# freesoc2_shield.net
KiCad netlist of a schematic drawn in EAGLE
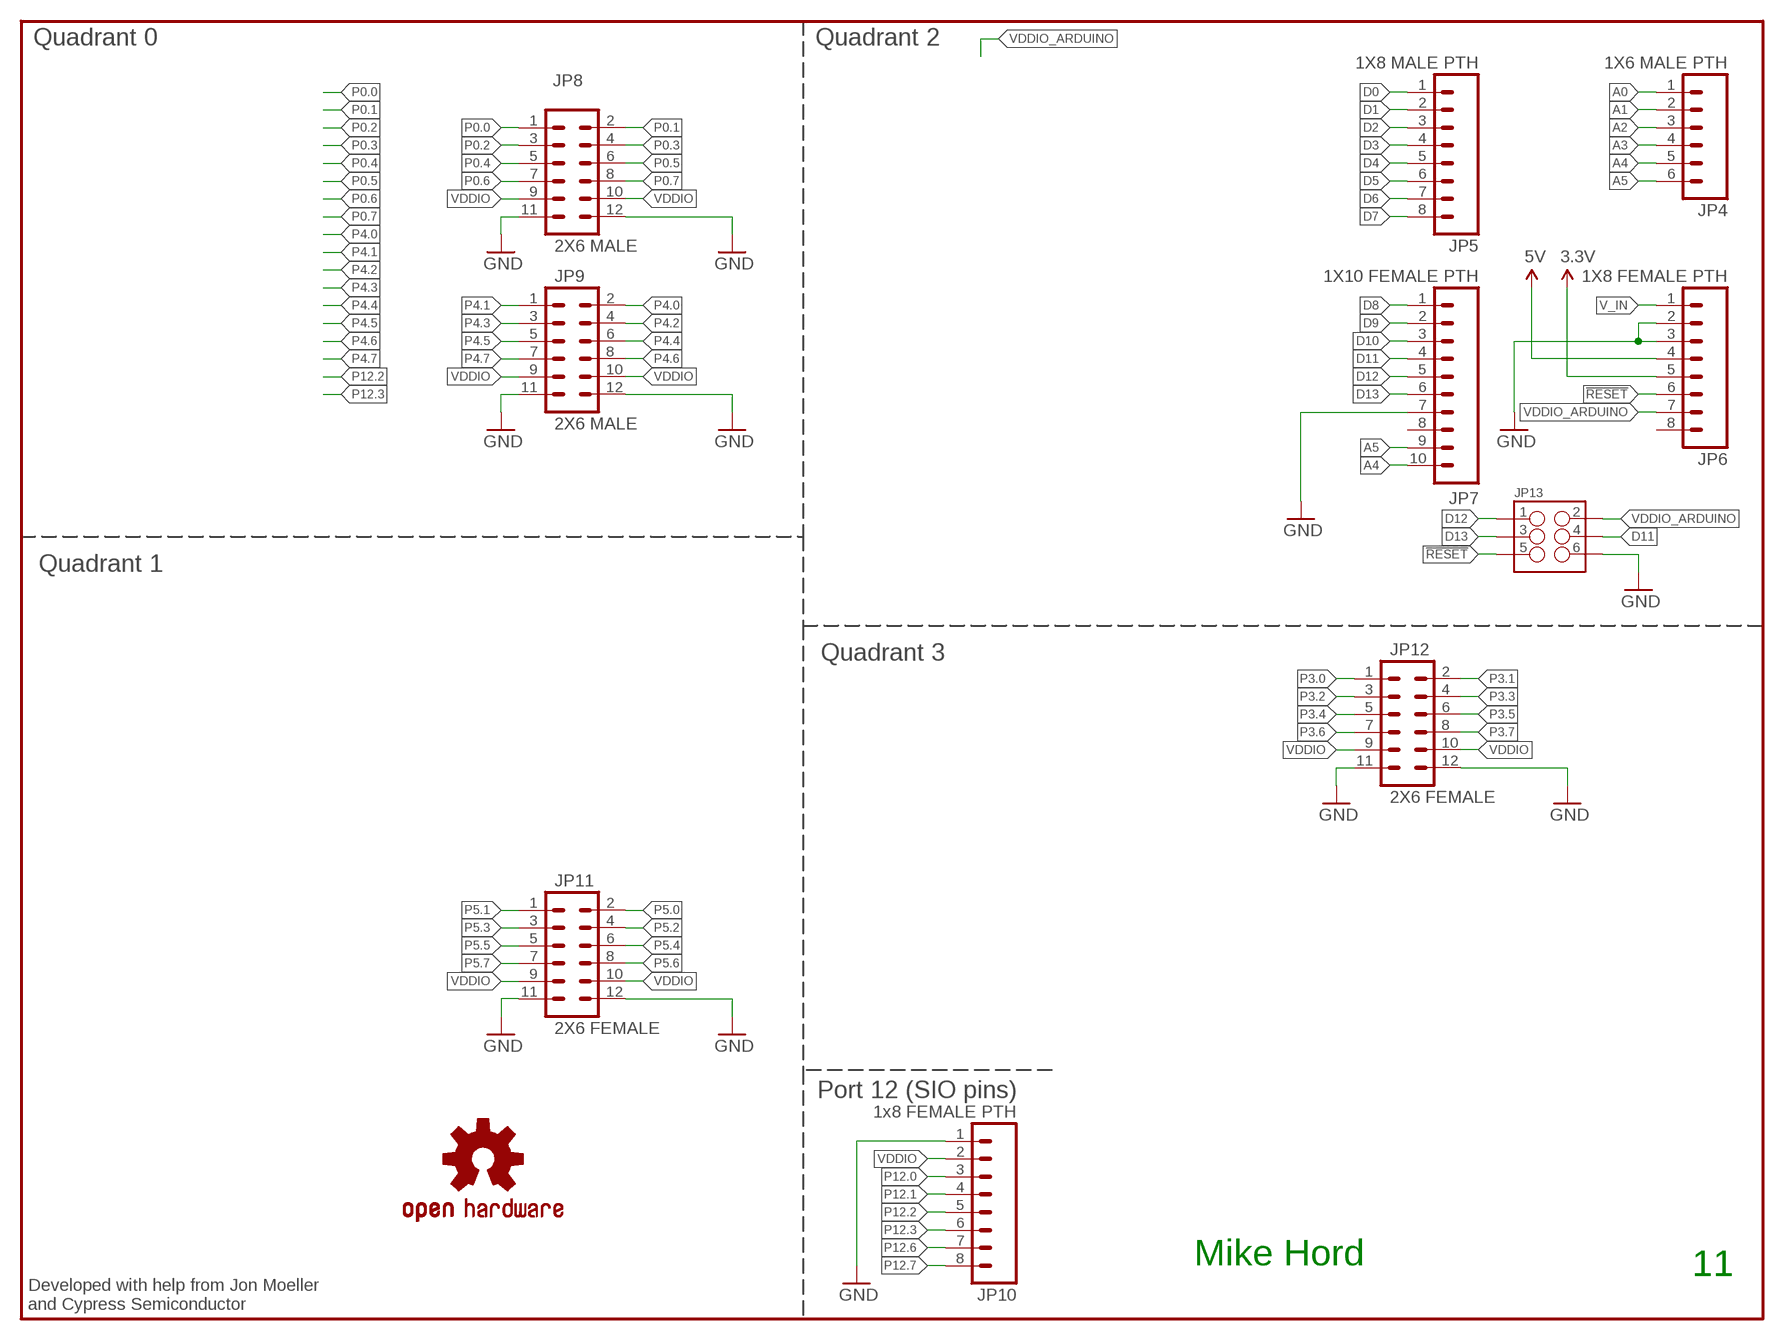
[diagram p0: schematic, sheet 1]

(export (version "E")
  (design (tool "Eeschema 10.0.6"))
  (components
    (comp (ref "FRAME1")
      (value "FRAME-LETTERNO_PACKAGE")
      (footprint "eagle-import:DUMMY")
      (fields (field (name "DESIGNER") "Nobody"))
      (libsource (lib "eagle-import") (part "FRAME-LETTERNO_PACKAGE"))
    )
    (comp (ref "JP4")
      (value "1X6 MALE PTH")
      (footprint "eagle-import:1X06-SIP_LOCK")
      (libsource (lib "eagle-import") (part "M06SIP_LOCK"))
    )
    (comp (ref "JP5")
      (value "1X8 MALE PTH")
      (footprint "eagle-import:1X08_LOCK")
      (libsource (lib "eagle-import") (part "M08LOCK"))
    )
    (comp (ref "JP6")
      (value "1X8 FEMALE PTH")
      (footprint "eagle-import:1X08_LOCK")
      (libsource (lib "eagle-import") (part "M08LOCK"))
    )
    (comp (ref "JP7")
      (value "1X10 FEMALE PTH")
      (footprint "eagle-import:1X10_LOCK")
      (libsource (lib "eagle-import") (part "M10LOCK"))
    )
    (comp (ref "JP8")
      (value "2X6 MALE")
      (footprint "eagle-import:2X6")
      (libsource (lib "eagle-import") (part "M06X2PTH_FEMALE"))
    )
    (comp (ref "JP9")
      (value "2X6 MALE")
      (footprint "eagle-import:2X6")
      (libsource (lib "eagle-import") (part "M06X2PTH_FEMALE"))
    )
    (comp (ref "JP10")
      (value "1x8 FEMALE PTH")
      (footprint "eagle-import:1X08_LOCK")
      (libsource (lib "eagle-import") (part "M08LOCK"))
    )
    (comp (ref "JP11")
      (value "2X6 FEMALE")
      (footprint "eagle-import:2X6")
      (libsource (lib "eagle-import") (part "M06X2PTH_FEMALE"))
    )
    (comp (ref "JP12")
      (value "2X6 FEMALE")
      (footprint "eagle-import:2X6")
      (libsource (lib "eagle-import") (part "M06X2PTH_FEMALE"))
    )
    (comp (ref "JP13")
      (value "M03X22X3_SILK_MALE_PTH")
      (footprint "eagle-import:2X3")
      (libsource (lib "eagle-import") (part "M03X22X3_SILK_MALE_PTH"))
    )
    (comp (ref "LOGO2")
      (value "OSHW-LOGOS")
      (footprint "eagle-import:OSHW-LOGO-S")
      (libsource (lib "eagle-import") (part "OSHW-LOGOS"))
    )
  )
  (nets
    (net (code "1") (name "/~{RESET}") (class "Default")
      (node (ref "JP13") (pin "5") (pinfunction "5_5") (pintype "bidirectional"))
      (node (ref "JP6") (pin "6") (pinfunction "6_6") (pintype "passive"))
    )
    (net (code "2") (name "3.3V") (class "Default")
      (node (ref "JP6") (pin "5") (pinfunction "5_5") (pintype "passive"))
    )
    (net (code "3") (name "5V") (class "Default")
      (node (ref "JP6") (pin "4") (pinfunction "4_4") (pintype "passive"))
    )
    (net (code "4") (name "A0") (class "Default")
      (node (ref "JP4") (pin "1") (pinfunction "1_1") (pintype "passive"))
    )
    (net (code "5") (name "A1") (class "Default")
      (node (ref "JP4") (pin "2") (pinfunction "2_2") (pintype "passive"))
    )
    (net (code "6") (name "A2") (class "Default")
      (node (ref "JP4") (pin "3") (pinfunction "3_3") (pintype "passive"))
    )
    (net (code "7") (name "A3") (class "Default")
      (node (ref "JP4") (pin "4") (pinfunction "4_4") (pintype "passive"))
    )
    (net (code "8") (name "A4") (class "Default")
      (node (ref "JP4") (pin "5") (pinfunction "5_5") (pintype "passive"))
      (node (ref "JP7") (pin "10") (pinfunction "10_10") (pintype "passive"))
    )
    (net (code "9") (name "A5") (class "Default")
      (node (ref "JP4") (pin "6") (pinfunction "6_6") (pintype "passive"))
      (node (ref "JP7") (pin "9") (pinfunction "9_9") (pintype "passive"))
    )
    (net (code "10") (name "D0") (class "Default")
      (node (ref "JP5") (pin "1") (pinfunction "1_1") (pintype "passive"))
    )
    (net (code "11") (name "D1") (class "Default")
      (node (ref "JP5") (pin "2") (pinfunction "2_2") (pintype "passive"))
    )
    (net (code "12") (name "D2") (class "Default")
      (node (ref "JP5") (pin "3") (pinfunction "3_3") (pintype "passive"))
    )
    (net (code "13") (name "D3") (class "Default")
      (node (ref "JP5") (pin "4") (pinfunction "4_4") (pintype "passive"))
    )
    (net (code "14") (name "D4") (class "Default")
      (node (ref "JP5") (pin "5") (pinfunction "5_5") (pintype "passive"))
    )
    (net (code "15") (name "D5") (class "Default")
      (node (ref "JP5") (pin "6") (pinfunction "6_6") (pintype "passive"))
    )
    (net (code "16") (name "D6") (class "Default")
      (node (ref "JP5") (pin "7") (pinfunction "7_7") (pintype "passive"))
    )
    (net (code "17") (name "D7") (class "Default")
      (node (ref "JP5") (pin "8") (pinfunction "8_8") (pintype "passive"))
    )
    (net (code "18") (name "D8") (class "Default")
      (node (ref "JP7") (pin "1") (pinfunction "1_1") (pintype "passive"))
    )
    (net (code "19") (name "D9") (class "Default")
      (node (ref "JP7") (pin "2") (pinfunction "2_2") (pintype "passive"))
    )
    (net (code "20") (name "D10") (class "Default")
      (node (ref "JP7") (pin "3") (pinfunction "3_3") (pintype "passive"))
    )
    (net (code "21") (name "D11") (class "Default")
      (node (ref "JP13") (pin "4") (pinfunction "4_4") (pintype "bidirectional"))
      (node (ref "JP7") (pin "4") (pinfunction "4_4") (pintype "passive"))
    )
    (net (code "22") (name "D12") (class "Default")
      (node (ref "JP13") (pin "1") (pinfunction "1_1") (pintype "bidirectional"))
      (node (ref "JP7") (pin "5") (pinfunction "5_5") (pintype "passive"))
    )
    (net (code "23") (name "D13") (class "Default")
      (node (ref "JP13") (pin "3") (pinfunction "3_3") (pintype "bidirectional"))
      (node (ref "JP7") (pin "6") (pinfunction "6_6") (pintype "passive"))
    )
    (net (code "24") (name "GND") (class "Default")
      (node (ref "JP10") (pin "1") (pinfunction "1_1") (pintype "passive"))
      (node (ref "JP11") (pin "11") (pinfunction "11_11") (pintype "passive"))
      (node (ref "JP11") (pin "12") (pinfunction "12_12") (pintype "passive"))
      (node (ref "JP12") (pin "11") (pinfunction "11_11") (pintype "passive"))
      (node (ref "JP12") (pin "12") (pinfunction "12_12") (pintype "passive"))
      (node (ref "JP13") (pin "6") (pinfunction "6_6") (pintype "bidirectional"))
      (node (ref "JP6") (pin "2") (pinfunction "2_2") (pintype "passive"))
      (node (ref "JP6") (pin "3") (pinfunction "3_3") (pintype "passive"))
      (node (ref "JP7") (pin "7") (pinfunction "7_7") (pintype "passive"))
      (node (ref "JP8") (pin "11") (pinfunction "11_11") (pintype "passive"))
      (node (ref "JP8") (pin "12") (pinfunction "12_12") (pintype "passive"))
      (node (ref "JP9") (pin "11") (pinfunction "11_11") (pintype "passive"))
      (node (ref "JP9") (pin "12") (pinfunction "12_12") (pintype "passive"))
    )
    (net (code "25") (name "P0.0") (class "Default")
      (node (ref "JP8") (pin "1") (pinfunction "1_1") (pintype "passive"))
    )
    (net (code "26") (name "P0.1") (class "Default")
      (node (ref "JP8") (pin "2") (pinfunction "2_2") (pintype "passive"))
    )
    (net (code "27") (name "P0.2") (class "Default")
      (node (ref "JP8") (pin "3") (pinfunction "3_3") (pintype "passive"))
    )
    (net (code "28") (name "P0.3") (class "Default")
      (node (ref "JP8") (pin "4") (pinfunction "4_4") (pintype "passive"))
    )
    (net (code "29") (name "P0.4") (class "Default")
      (node (ref "JP8") (pin "5") (pinfunction "5_5") (pintype "passive"))
    )
    (net (code "30") (name "P0.5") (class "Default")
      (node (ref "JP8") (pin "6") (pinfunction "6_6") (pintype "passive"))
    )
    (net (code "31") (name "P0.6") (class "Default")
      (node (ref "JP8") (pin "7") (pinfunction "7_7") (pintype "passive"))
    )
    (net (code "32") (name "P0.7") (class "Default")
      (node (ref "JP8") (pin "8") (pinfunction "8_8") (pintype "passive"))
    )
    (net (code "33") (name "P3.0") (class "Default")
      (node (ref "JP12") (pin "1") (pinfunction "1_1") (pintype "passive"))
    )
    (net (code "34") (name "P3.1") (class "Default")
      (node (ref "JP12") (pin "2") (pinfunction "2_2") (pintype "passive"))
    )
    (net (code "35") (name "P3.2") (class "Default")
      (node (ref "JP12") (pin "3") (pinfunction "3_3") (pintype "passive"))
    )
    (net (code "36") (name "P3.3") (class "Default")
      (node (ref "JP12") (pin "4") (pinfunction "4_4") (pintype "passive"))
    )
    (net (code "37") (name "P3.4") (class "Default")
      (node (ref "JP12") (pin "5") (pinfunction "5_5") (pintype "passive"))
    )
    (net (code "38") (name "P3.5") (class "Default")
      (node (ref "JP12") (pin "6") (pinfunction "6_6") (pintype "passive"))
    )
    (net (code "39") (name "P3.6") (class "Default")
      (node (ref "JP12") (pin "7") (pinfunction "7_7") (pintype "passive"))
    )
    (net (code "40") (name "P3.7") (class "Default")
      (node (ref "JP12") (pin "8") (pinfunction "8_8") (pintype "passive"))
    )
    (net (code "41") (name "P4.0") (class "Default")
      (node (ref "JP9") (pin "2") (pinfunction "2_2") (pintype "passive"))
    )
    (net (code "42") (name "P4.1") (class "Default")
      (node (ref "JP9") (pin "1") (pinfunction "1_1") (pintype "passive"))
    )
    (net (code "43") (name "P4.2") (class "Default")
      (node (ref "JP9") (pin "4") (pinfunction "4_4") (pintype "passive"))
    )
    (net (code "44") (name "P4.3") (class "Default")
      (node (ref "JP9") (pin "3") (pinfunction "3_3") (pintype "passive"))
    )
    (net (code "45") (name "P4.4") (class "Default")
      (node (ref "JP9") (pin "6") (pinfunction "6_6") (pintype "passive"))
    )
    (net (code "46") (name "P4.5") (class "Default")
      (node (ref "JP9") (pin "5") (pinfunction "5_5") (pintype "passive"))
    )
    (net (code "47") (name "P4.6") (class "Default")
      (node (ref "JP9") (pin "8") (pinfunction "8_8") (pintype "passive"))
    )
    (net (code "48") (name "P4.7") (class "Default")
      (node (ref "JP9") (pin "7") (pinfunction "7_7") (pintype "passive"))
    )
    (net (code "49") (name "P5.0") (class "Default")
      (node (ref "JP11") (pin "2") (pinfunction "2_2") (pintype "passive"))
    )
    (net (code "50") (name "P5.1") (class "Default")
      (node (ref "JP11") (pin "1") (pinfunction "1_1") (pintype "passive"))
    )
    (net (code "51") (name "P5.2") (class "Default")
      (node (ref "JP11") (pin "4") (pinfunction "4_4") (pintype "passive"))
    )
    (net (code "52") (name "P5.3") (class "Default")
      (node (ref "JP11") (pin "3") (pinfunction "3_3") (pintype "passive"))
    )
    (net (code "53") (name "P5.4") (class "Default")
      (node (ref "JP11") (pin "6") (pinfunction "6_6") (pintype "passive"))
    )
    (net (code "54") (name "P5.5") (class "Default")
      (node (ref "JP11") (pin "5") (pinfunction "5_5") (pintype "passive"))
    )
    (net (code "55") (name "P5.6") (class "Default")
      (node (ref "JP11") (pin "8") (pinfunction "8_8") (pintype "passive"))
    )
    (net (code "56") (name "P5.7") (class "Default")
      (node (ref "JP11") (pin "7") (pinfunction "7_7") (pintype "passive"))
    )
    (net (code "57") (name "P12.0") (class "Default")
      (node (ref "JP10") (pin "3") (pinfunction "3_3") (pintype "passive"))
    )
    (net (code "58") (name "P12.1") (class "Default")
      (node (ref "JP10") (pin "4") (pinfunction "4_4") (pintype "passive"))
    )
    (net (code "59") (name "P12.2") (class "Default")
      (node (ref "JP10") (pin "5") (pinfunction "5_5") (pintype "passive"))
    )
    (net (code "60") (name "P12.3") (class "Default")
      (node (ref "JP10") (pin "6") (pinfunction "6_6") (pintype "passive"))
    )
    (net (code "61") (name "P12.6") (class "Default")
      (node (ref "JP10") (pin "7") (pinfunction "7_7") (pintype "passive"))
    )
    (net (code "62") (name "P12.7") (class "Default")
      (node (ref "JP10") (pin "8") (pinfunction "8_8") (pintype "passive"))
    )
    (net (code "63") (name "VDDIO") (class "Default")
      (node (ref "JP10") (pin "2") (pinfunction "2_2") (pintype "passive"))
      (node (ref "JP11") (pin "10") (pinfunction "10_10") (pintype "passive"))
      (node (ref "JP11") (pin "9") (pinfunction "9_9") (pintype "passive"))
      (node (ref "JP12") (pin "10") (pinfunction "10_10") (pintype "passive"))
      (node (ref "JP12") (pin "9") (pinfunction "9_9") (pintype "passive"))
      (node (ref "JP8") (pin "10") (pinfunction "10_10") (pintype "passive"))
      (node (ref "JP8") (pin "9") (pinfunction "9_9") (pintype "passive"))
      (node (ref "JP9") (pin "10") (pinfunction "10_10") (pintype "passive"))
      (node (ref "JP9") (pin "9") (pinfunction "9_9") (pintype "passive"))
    )
    (net (code "64") (name "VDDIO_ARDUINO") (class "Default")
      (node (ref "JP13") (pin "2") (pinfunction "2_2") (pintype "bidirectional"))
      (node (ref "JP6") (pin "7") (pinfunction "7_7") (pintype "passive"))
    )
    (net (code "65") (name "V_IN") (class "Default")
      (node (ref "JP6") (pin "1") (pinfunction "1_1") (pintype "passive"))
    )
    (net (code "66") (name "unconnected-(JP6-Pad8)") (class "Default")
      (node (ref "JP6") (pin "8") (pinfunction "8_8") (pintype "passive"))
    )
    (net (code "67") (name "unconnected-(JP7-Pad8)") (class "Default")
      (node (ref "JP7") (pin "8") (pinfunction "8_8") (pintype "passive"))
    )
  )
)
